# sensor_board_v0_91.net
KiCad netlist of a schematic drawn in EAGLE
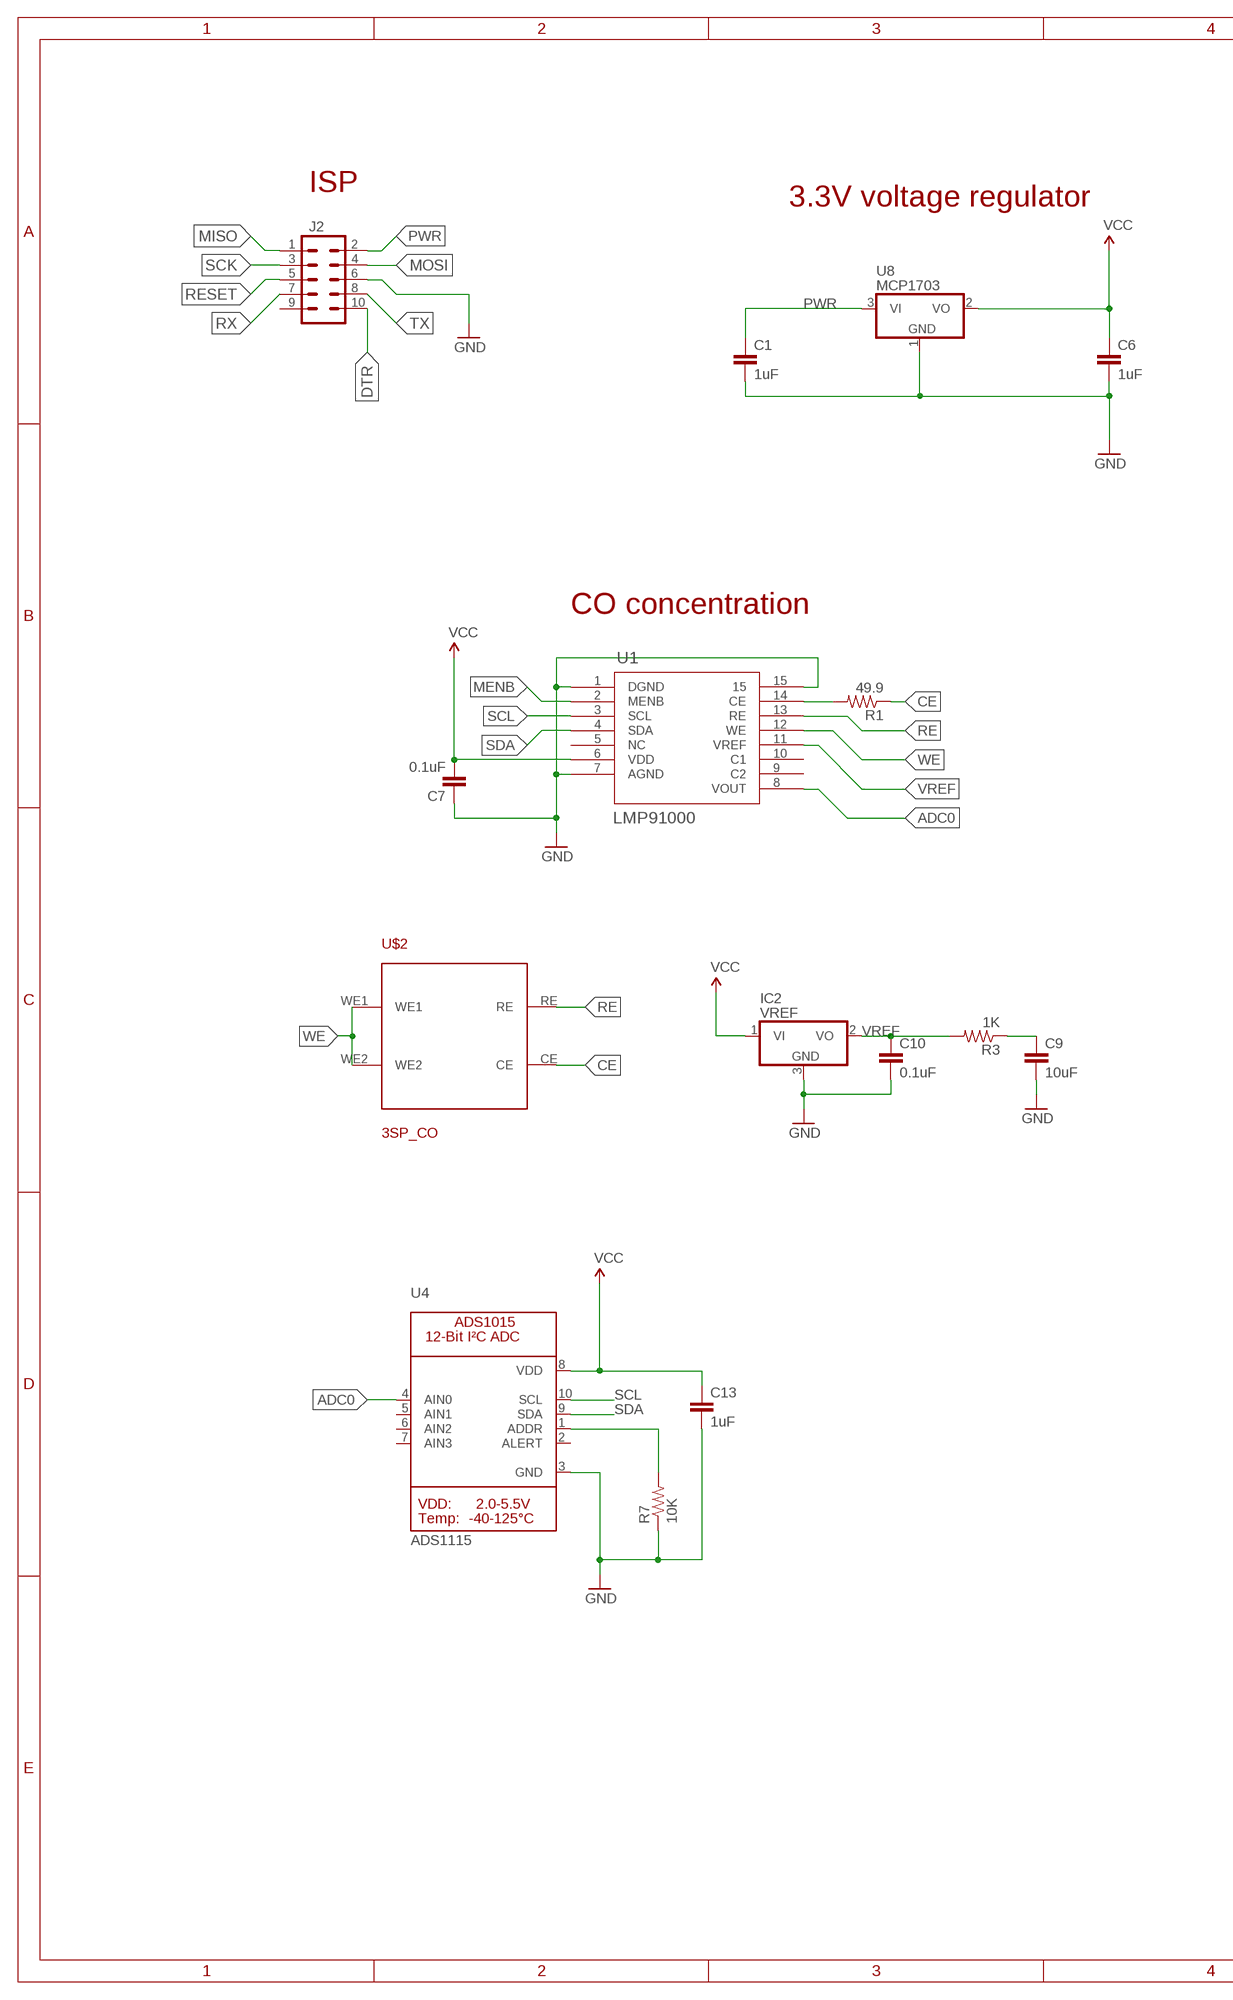
[diagram p0: schematic, sheet 1, part 1 of 2]
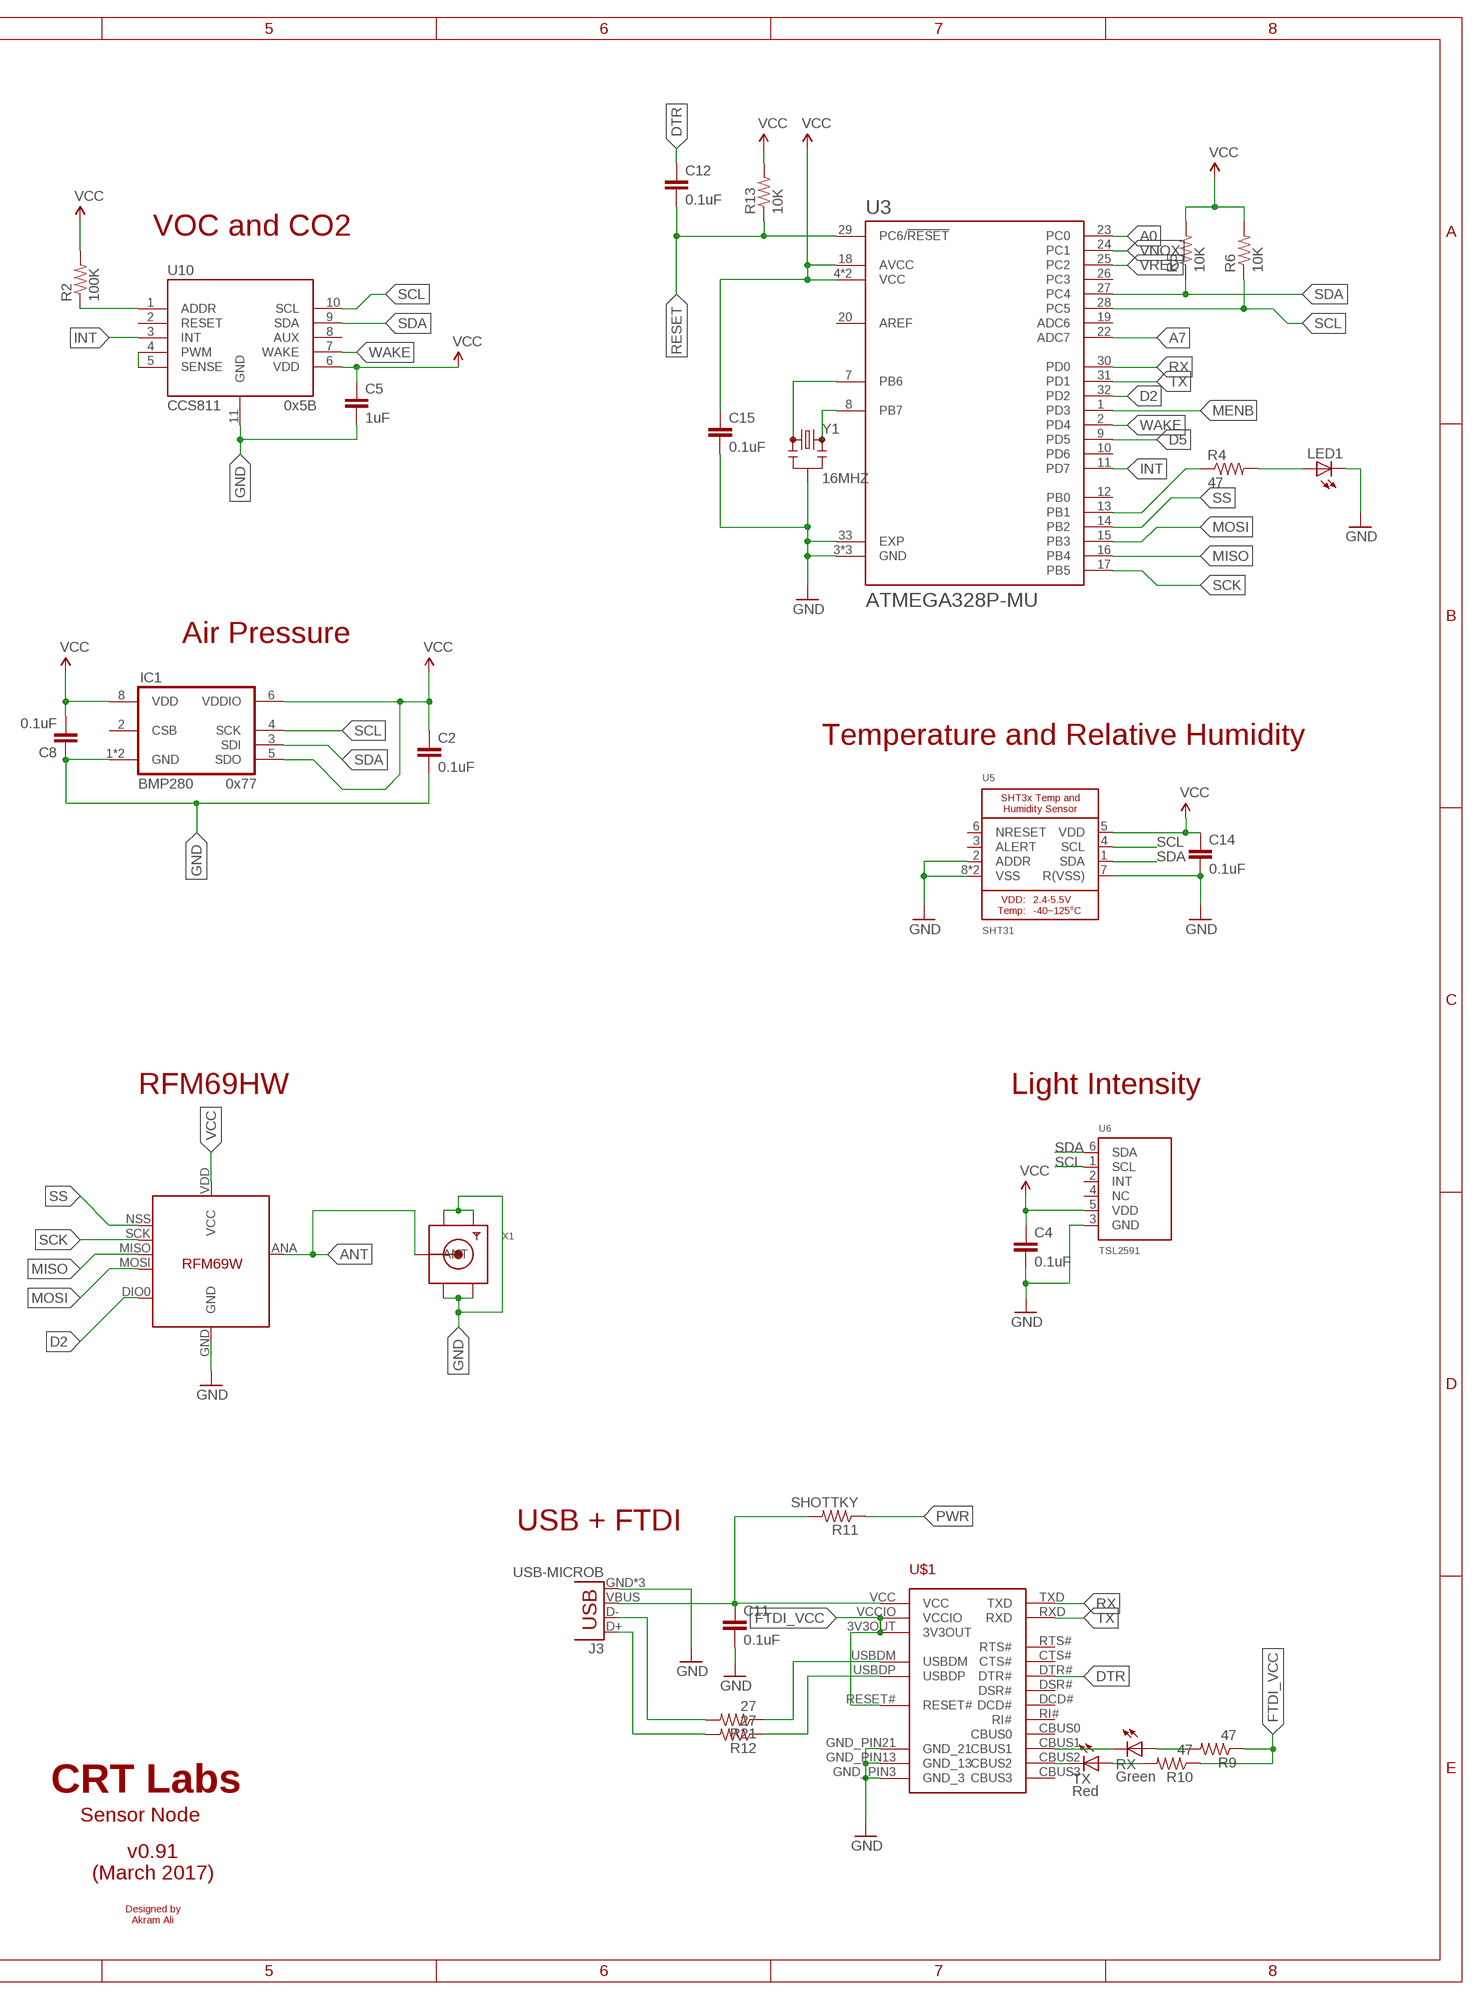
[diagram p1: schematic, sheet 1, part 2 of 2]

(export (version "E")
  (design (tool "Eeschema 10.0.6"))
  (components
    (comp (ref "C1")
      (value "1uF")
      (footprint "eagle-import:0805")
      (fields (field (name "MPN") "CC0805KKX7R7BB105"))
      (libsource (lib "eagle-import") (part "CAP0805"))
    )
    (comp (ref "C2")
      (value "0.1uF")
      (footprint "eagle-import:0805")
      (fields (field (name "MPN") "AC0805KRX7R9BB104"))
      (libsource (lib "eagle-import") (part "SparkFun-Passives_CAP0805"))
    )
    (comp (ref "C4")
      (value "0.1uF")
      (footprint "eagle-import:0805")
      (fields (field (name "MPN") "AC0805KRX7R9BB104"))
      (libsource (lib "eagle-import") (part "SparkFun-Passives_CAP0805"))
    )
    (comp (ref "C5")
      (value "1uF")
      (footprint "eagle-import:0805")
      (fields (field (name "MPN") "CC0805KKX7R7BB105"))
      (libsource (lib "eagle-import") (part "SparkFun-Passives_CAP0805"))
    )
    (comp (ref "C6")
      (value "1uF")
      (footprint "eagle-import:0805")
      (fields (field (name "MPN") "CC0805KKX7R7BB105"))
      (libsource (lib "eagle-import") (part "CAP0805"))
    )
    (comp (ref "C7")
      (value "0.1uF")
      (footprint "eagle-import:0805")
      (fields (field (name "MPN") "AC0805KRX7R9BB104"))
      (libsource (lib "eagle-import") (part "SparkFun-Passives_CAP0805"))
    )
    (comp (ref "C8")
      (value "0.1uF")
      (footprint "eagle-import:0805")
      (fields (field (name "MPN") "AC0805KRX7R9BB104"))
      (libsource (lib "eagle-import") (part "SparkFun-Passives_CAP0805"))
    )
    (comp (ref "C9")
      (value "10uF")
      (footprint "eagle-import:0805")
      (fields (field (name "MPN") "CC0805ZKY5V6BB106"))
      (libsource (lib "eagle-import") (part "SparkFun-Passives_CAP0805"))
    )
    (comp (ref "C10")
      (value "0.1uF")
      (footprint "eagle-import:0805")
      (fields (field (name "MPN") "AC0805KRX7R9BB104"))
      (libsource (lib "eagle-import") (part "SparkFun-Passives_CAP0805"))
    )
    (comp (ref "C11")
      (value "0.1uF")
      (footprint "eagle-import:0805")
      (fields (field (name "MPN") "AC0805KRX7R9BB104"))
      (libsource (lib "eagle-import") (part "CAP0805"))
    )
    (comp (ref "C12")
      (value "0.1uF")
      (footprint "eagle-import:0805")
      (fields (field (name "MPN") "AC0805KRX7R9BB104"))
      (libsource (lib "eagle-import") (part "SparkFun-Passives_CAP0805"))
    )
    (comp (ref "C13")
      (value "1uF")
      (footprint "eagle-import:0805")
      (fields (field (name "MPN") "CC0805KKX7R7BB105"))
      (libsource (lib "eagle-import") (part "SparkFun-Passives_CAP0805"))
    )
    (comp (ref "C14")
      (value "0.1uF")
      (footprint "eagle-import:0805")
      (fields (field (name "MPN") "AC0805KRX7R9BB104"))
      (libsource (lib "eagle-import") (part "SparkFun-Passives_CAP0805"))
    )
    (comp (ref "C15")
      (value "0.1uF")
      (footprint "eagle-import:0805")
      (fields (field (name "MPN") "AC0805KRX7R9BB104"))
      (libsource (lib "eagle-import") (part "SparkFun-Passives_CAP0805"))
    )
    (comp (ref "IC1")
      (value "BMP280")
      (footprint "eagle-import:BMP280")
      (libsource (lib "eagle-import") (part "BMP280"))
    )
    (comp (ref "IC2")
      (value "VREF")
      (footprint "eagle-import:SOT23")
      (fields (field (name "MPN") "ISL60002DIH320Z-TK"))
      (libsource (lib "eagle-import") (part "ISL60002DIH320ZCB"))
    )
    (comp (ref "J2")
      (value "M05X2PTH")
      (footprint "eagle-import:AVR_ICSP")
      (libsource (lib "eagle-import") (part "M05X2PTH"))
    )
    (comp (ref "J3")
      (value "USB-MICROB")
      (footprint "eagle-import:USB-MICROB")
      (fields (field (name "MPN") "CONN-09505"))
      (libsource (lib "eagle-import") (part "USB-MICROB"))
    )
    (comp (ref "LED1")
      (value "LEDCHIPLED_0805")
      (footprint "eagle-import:CHIPLED_0805")
      (fields (field (name "MPN") "150080BS75000"))
      (libsource (lib "eagle-import") (part "LEDCHIPLED_0805"))
    )
    (comp (ref "R1")
      (value "49.9")
      (footprint "eagle-import:0805")
      (fields (field (name "MPN") "RC0805FR-0749R9L"))
      (libsource (lib "eagle-import") (part "RESISTOR0805-RES"))
    )
    (comp (ref "R2")
      (value "100K")
      (footprint "eagle-import:0805")
      (fields (field (name "MPN") "311-100KCRCT-ND"))
      (libsource (lib "eagle-import") (part "RESISTOR0805-RES"))
    )
    (comp (ref "R3")
      (value "1K")
      (footprint "eagle-import:0805")
      (fields (field (name "MPN") "RC0805JR-071KL"))
      (libsource (lib "eagle-import") (part "RESISTOR0805-RES"))
    )
    (comp (ref "R4")
      (value "47")
      (footprint "eagle-import:0805")
      (fields (field (name "MPN") "RC0805JR-0747RL"))
      (libsource (lib "eagle-import") (part "SparkFun-Resistors_RESISTOR0805-RES"))
    )
    (comp (ref "R5")
      (value "10K")
      (footprint "eagle-import:0805")
      (fields (field (name "MPN") "RC0805JR-0710KL"))
      (libsource (lib "eagle-import") (part "SparkFun-Resistors_RESISTOR0805-RES"))
    )
    (comp (ref "R6")
      (value "10K")
      (footprint "eagle-import:0805")
      (fields (field (name "MPN") "RC0805JR-0710KL"))
      (libsource (lib "eagle-import") (part "SparkFun-Resistors_RESISTOR0805-RES"))
    )
    (comp (ref "R7")
      (value "10K")
      (footprint "eagle-import:0805")
      (fields (field (name "MPN") "RC0805JR-0710KL"))
      (libsource (lib "eagle-import") (part "SparkFun-Resistors_RESISTOR0805-RES"))
    )
    (comp (ref "R9")
      (value "47")
      (footprint "eagle-import:0805")
      (fields (field (name "MPN") "RC0805JR-0747RL"))
      (libsource (lib "eagle-import") (part "RESISTOR0805-RES"))
    )
    (comp (ref "R10")
      (value "47")
      (footprint "eagle-import:0805")
      (fields (field (name "MPN") "RC0805JR-0747RL"))
      (libsource (lib "eagle-import") (part "RESISTOR0805-RES"))
    )
    (comp (ref "R11")
      (value "SHOTTKY")
      (footprint "eagle-import:0805")
      (fields (field (name "MPN") "SD0805S020S0R5"))
      (libsource (lib "eagle-import") (part "RESISTOR0805-RES"))
    )
    (comp (ref "R12")
      (value "27")
      (footprint "eagle-import:0805")
      (fields (field (name "MPN") "RC0805FR-0727RL"))
      (libsource (lib "eagle-import") (part "RESISTOR0805-RES"))
    )
    (comp (ref "R13")
      (value "10K")
      (footprint "eagle-import:0805")
      (fields (field (name "MPN") "RC0805JR-0710KL"))
      (libsource (lib "eagle-import") (part "RESISTOR0805-RES"))
    )
    (comp (ref "R21")
      (value "27")
      (footprint "eagle-import:0805")
      (fields (field (name "MPN") "RC0805FR-0727RL"))
      (libsource (lib "eagle-import") (part "RESISTOR0805-RES"))
    )
    (comp (ref "RX")
      (value "Green")
      (footprint "eagle-import:CHIPLED_0805")
      (fields (field (name "MPN") "LG R971-KN-1"))
      (libsource (lib "eagle-import") (part "LEDCHIPLED_0805"))
    )
    (comp (ref "TX")
      (value "Red")
      (footprint "eagle-import:CHIPLED_0805")
      (fields (field (name "MPN") "LH R974-LP-1"))
      (libsource (lib "eagle-import") (part "LEDCHIPLED_0805"))
    )
    (comp (ref "U$1")
      (value "FT231XQ-R")
      (footprint "eagle-import:FTDI_FT231XQ-R_PACKAGE")
      (libsource (lib "eagle-import") (part "FT231XQ-R"))
    )
    (comp (ref "U$2")
      (value "3SP_CO")
      (footprint "eagle-import:3SP_CO_PIN_PACKAGE")
      (fields (field (name "MPN") "3SP CO"))
      (libsource (lib "eagle-import") (part "3SP_CO"))
    )
    (comp (ref "U1")
      (value "LMP91000")
      (footprint "eagle-import:SDA14B")
      (fields
        (field (name "MANUFACTURER") "Texas Instruments")
        (field (name "MANUFACTURER_PART_NUMBER") "lmp91000_nhl_14")
      )
      (libsource (lib "eagle-import") (part "LMP91000_NHL_14"))
    )
    (comp (ref "U3")
      (value "ATMEGA328P-MU")
      (footprint "eagle-import:QFN50P500X500X100-33N")
      (fields (field (name "MF") "Atmel"))
      (libsource (lib "eagle-import") (part "ATMEGA328P-MU"))
    )
    (comp (ref "U4")
      (value "ADS1115")
      (footprint "eagle-import:MSOP10")
      (libsource (lib "eagle-import") (part "ADC_ADS1015"))
    )
    (comp (ref "U5")
      (value "SHT31")
      (footprint "eagle-import:SHT3X")
      (libsource (lib "eagle-import") (part "SHT3X"))
    )
    (comp (ref "U6")
      (value "TSL2591")
      (footprint "eagle-import:DFN6_TAOS")
      (libsource (lib "eagle-import") (part "LIGHT_TSL2591"))
    )
    (comp (ref "U8")
      (value "MCP1703")
      (footprint "eagle-import:SOT23")
      (fields (field (name "MPN") "MCP1703T-2502E/CB"))
      (libsource (lib "eagle-import") (part "MCP1703CB"))
    )
    (comp (ref "U10")
      (value "CCS811")
      (footprint "eagle-import:LGA")
      (libsource (lib "eagle-import") (part "CCS811-I2C"))
    )
    (comp (ref "U11")
      (value "RFM69HW")
      (footprint "eagle-import:LOWPOWERLAB_RFM69W-MINPADS")
      (libsource (lib "eagle-import") (part "LOWPOWERLAB_RFM69"))
    )
    (comp (ref "X1")
      (value "SMACONNECTOR_EDGE")
      (footprint "eagle-import:SMA_EDGELAUNCH")
      (fields (field (name "MPN") "WRL-00593"))
      (libsource (lib "eagle-import") (part "SMACONNECTOR_EDGE"))
    )
    (comp (ref "Y1")
      (value "16MHZ")
      (footprint "eagle-import:RESONATOR-SMD")
      (fields (field (name "MPN") "CSTCE16M0V53-R0"))
      (libsource (lib "eagle-import") (part "RESONATOR16MHZ"))
    )
  )
  (nets
    (net (code "1") (name "A0") (class "Default")
      (node (ref "U3") (pin "23") (pinfunction "PC0_23") (pintype "bidirectional"))
    )
    (net (code "2") (name "A7") (class "Default")
      (node (ref "U3") (pin "22") (pinfunction "ADC7_22") (pintype "bidirectional"))
    )
    (net (code "3") (name "ADC0") (class "Default")
      (node (ref "U1") (pin "8") (pinfunction "VOUT_8") (pintype "output"))
      (node (ref "U4") (pin "4") (pinfunction "AIN0_4") (pintype "bidirectional"))
    )
    (net (code "4") (name "ANT") (class "Default")
      (node (ref "U11") (pin "ANA") (pinfunction "ANT_ANA") (pintype "passive"))
      (node (ref "X1") (pin "P") (pinfunction "ANT_P") (pintype "bidirectional"))
    )
    (net (code "5") (name "CE") (class "Default")
      (node (ref "R1") (pin "1") (pinfunction "1_1") (pintype "passive"))
      (node (ref "U$2") (pin "CE") (pinfunction "CE_CE") (pintype "bidirectional"))
    )
    (net (code "6") (name "D2") (class "Default")
      (node (ref "U11") (pin "DIO0") (pinfunction "DIO0_DIO0") (pintype "open_collector"))
      (node (ref "U3") (pin "32") (pinfunction "PD2_32") (pintype "bidirectional"))
    )
    (net (code "7") (name "D5") (class "Default")
      (node (ref "U3") (pin "9") (pinfunction "PD5_9") (pintype "bidirectional"))
    )
    (net (code "8") (name "DTR") (class "Default")
      (node (ref "C12") (pin "1") (pinfunction "1_1") (pintype "passive"))
      (node (ref "J2") (pin "10") (pinfunction "10_10") (pintype "passive"))
      (node (ref "U$1") (pin "DTR#") (pinfunction "DTR#_DTR#") (pintype "bidirectional"))
    )
    (net (code "9") (name "FTDI_VCC") (class "Default")
      (node (ref "R10") (pin "1") (pinfunction "1_1") (pintype "passive"))
      (node (ref "R9") (pin "1") (pinfunction "1_1") (pintype "passive"))
      (node (ref "U$1") (pin "3V3OUT") (pinfunction "3V3OUT_3V3OUT") (pintype "bidirectional"))
      (node (ref "U$1") (pin "RESET#") (pinfunction "RESET#_RESET#") (pintype "bidirectional"))
      (node (ref "U$1") (pin "VCCIO") (pinfunction "VCCIO_VCCIO") (pintype "bidirectional"))
    )
    (net (code "10") (name "GND") (class "Default")
      (node (ref "C1") (pin "2") (pinfunction "2_2") (pintype "passive"))
      (node (ref "C10") (pin "2") (pinfunction "2_2") (pintype "passive"))
      (node (ref "C11") (pin "2") (pinfunction "2_2") (pintype "passive"))
      (node (ref "C13") (pin "2") (pinfunction "2_2") (pintype "passive"))
      (node (ref "C14") (pin "2") (pinfunction "2_2") (pintype "passive"))
      (node (ref "C15") (pin "2") (pinfunction "2_2") (pintype "passive"))
      (node (ref "C2") (pin "2") (pinfunction "2_2") (pintype "passive"))
      (node (ref "C4") (pin "2") (pinfunction "2_2") (pintype "passive"))
      (node (ref "C5") (pin "2") (pinfunction "2_2") (pintype "passive"))
      (node (ref "C6") (pin "2") (pinfunction "2_2") (pintype "passive"))
      (node (ref "C7") (pin "1") (pinfunction "1_1") (pintype "passive"))
      (node (ref "C8") (pin "1") (pinfunction "1_1") (pintype "passive"))
      (node (ref "C9") (pin "2") (pinfunction "2_2") (pintype "passive"))
      (node (ref "IC1") (pin "1") (pinfunction "GND_1") (pintype "power_in"))
      (node (ref "IC1") (pin "7") (pinfunction "GND_7") (pintype "power_in"))
      (node (ref "IC2") (pin "3") (pinfunction "GND_3") (pintype "passive"))
      (node (ref "J2") (pin "6") (pinfunction "6_6") (pintype "passive"))
      (node (ref "J3") (pin "GND") (pinfunction "GND_GND") (pintype "bidirectional"))
      (node (ref "J3") (pin "MT1") (pinfunction "GND_MT1") (pintype "bidirectional"))
      (node (ref "J3") (pin "MT2") (pinfunction "GND_MT2") (pintype "bidirectional"))
      (node (ref "LED1") (pin "C") (pinfunction "C_C") (pintype "passive"))
      (node (ref "R7") (pin "1") (pinfunction "1_1") (pintype "passive"))
      (node (ref "U$1") (pin "GND_PIN13") (pinfunction "GND_13_GND_PIN13") (pintype "bidirectional"))
      (node (ref "U$1") (pin "GND_PIN21") (pinfunction "GND_21_GND_PIN21") (pintype "bidirectional"))
      (node (ref "U$1") (pin "GND_PIN3") (pinfunction "GND_3_GND_PIN3") (pintype "bidirectional"))
      (node (ref "U1") (pin "1") (pinfunction "DGND_1") (pintype "power_in"))
      (node (ref "U1") (pin "15") (pinfunction "15_15") (pintype "passive"))
      (node (ref "U1") (pin "7") (pinfunction "AGND_7") (pintype "power_in"))
      (node (ref "U10") (pin "11") (pinfunction "GND_11") (pintype "bidirectional"))
      (node (ref "U11") (pin "GND") (pinfunction "GND_GND") (pintype "power_in"))
      (node (ref "U3") (pin "21") (pinfunction "GND_21") (pintype "power_in"))
      (node (ref "U3") (pin "3") (pinfunction "GND_3") (pintype "power_in"))
      (node (ref "U3") (pin "33") (pinfunction "EXP_33") (pintype "power_in"))
      (node (ref "U3") (pin "5") (pinfunction "GND_5") (pintype "power_in"))
      (node (ref "U4") (pin "3") (pinfunction "GND_3") (pintype "bidirectional"))
      (node (ref "U5") (pin "2") (pinfunction "ADDR_2") (pintype "bidirectional"))
      (node (ref "U5") (pin "7") (pinfunction "R(VSS)_7") (pintype "bidirectional"))
      (node (ref "U5") (pin "8") (pinfunction "VSS_8") (pintype "power_in"))
      (node (ref "U5") (pin "THERMAL") (pinfunction "VSS_THERMAL") (pintype "power_in"))
      (node (ref "U6") (pin "3") (pinfunction "GND_3") (pintype "power_in"))
      (node (ref "U8") (pin "1") (pinfunction "GND_1") (pintype "passive"))
      (node (ref "X1") (pin "GND@1") (pinfunction "GND4_GND@1") (pintype "power_in"))
      (node (ref "X1") (pin "GND@2") (pinfunction "GND3_GND@2") (pintype "power_in"))
      (node (ref "X1") (pin "GND@3") (pinfunction "GND2_GND@3") (pintype "power_in"))
      (node (ref "X1") (pin "GND@4") (pinfunction "GND1_GND@4") (pintype "power_in"))
      (node (ref "Y1") (pin "2") (pinfunction "2_2") (pintype "passive"))
    )
    (net (code "11") (name "INT") (class "Default")
      (node (ref "U10") (pin "3") (pinfunction "INT_3") (pintype "bidirectional"))
      (node (ref "U3") (pin "11") (pinfunction "PD7_11") (pintype "bidirectional"))
    )
    (net (code "12") (name "MENB") (class "Default")
      (node (ref "U1") (pin "2") (pinfunction "MENB_2") (pintype "passive"))
      (node (ref "U3") (pin "1") (pinfunction "PD3_1") (pintype "bidirectional"))
    )
    (net (code "13") (name "MISO") (class "Default")
      (node (ref "J2") (pin "1") (pinfunction "1_1") (pintype "passive"))
      (node (ref "U11") (pin "MISO") (pinfunction "MISO_MISO") (pintype "input"))
      (node (ref "U3") (pin "16") (pinfunction "PB4_16") (pintype "bidirectional"))
    )
    (net (code "14") (name "MOSI") (class "Default")
      (node (ref "J2") (pin "4") (pinfunction "4_4") (pintype "passive"))
      (node (ref "U11") (pin "MOSI") (pinfunction "MOSI_MOSI") (pintype "output"))
      (node (ref "U3") (pin "15") (pinfunction "PB3_15") (pintype "bidirectional"))
    )
    (net (code "15") (name "Net-(C9-Pad1)") (class "Default")
      (node (ref "C9") (pin "1") (pinfunction "1_1") (pintype "passive"))
      (node (ref "R3") (pin "1") (pinfunction "1_1") (pintype "passive"))
    )
    (net (code "16") (name "Net-(C11-Pad1)") (class "Default")
      (node (ref "C11") (pin "1") (pinfunction "1_1") (pintype "passive"))
      (node (ref "J3") (pin "VBUS") (pinfunction "VBUS_VBUS") (pintype "bidirectional"))
      (node (ref "R11") (pin "2") (pinfunction "2_2") (pintype "passive"))
      (node (ref "U$1") (pin "VCC") (pinfunction "VCC_VCC") (pintype "bidirectional"))
    )
    (net (code "17") (name "Net-(J3-PadD+)") (class "Default")
      (node (ref "J3") (pin "D+") (pinfunction "D+_D+") (pintype "bidirectional"))
      (node (ref "R12") (pin "2") (pinfunction "2_2") (pintype "passive"))
    )
    (net (code "18") (name "Net-(J3-PadD-)") (class "Default")
      (node (ref "J3") (pin "D-") (pinfunction "D-_D-") (pintype "bidirectional"))
      (node (ref "R21") (pin "2") (pinfunction "2_2") (pintype "passive"))
    )
    (net (code "19") (name "Net-(LED1-PadA)") (class "Default")
      (node (ref "LED1") (pin "A") (pinfunction "A_A") (pintype "passive"))
      (node (ref "R4") (pin "2") (pinfunction "2_2") (pintype "passive"))
    )
    (net (code "20") (name "Net-(R9-Pad2)") (class "Default")
      (node (ref "R9") (pin "2") (pinfunction "2_2") (pintype "passive"))
      (node (ref "RX") (pin "A") (pinfunction "A_A") (pintype "passive"))
    )
    (net (code "21") (name "Net-(R10-Pad2)") (class "Default")
      (node (ref "R10") (pin "2") (pinfunction "2_2") (pintype "passive"))
      (node (ref "TX") (pin "A") (pinfunction "A_A") (pintype "passive"))
    )
    (net (code "22") (name "Net-(R12-Pad1)") (class "Default")
      (node (ref "R12") (pin "1") (pinfunction "1_1") (pintype "passive"))
      (node (ref "U$1") (pin "USBDP") (pinfunction "USBDP_USBDP") (pintype "bidirectional"))
    )
    (net (code "23") (name "Net-(R21-Pad1)") (class "Default")
      (node (ref "R21") (pin "1") (pinfunction "1_1") (pintype "passive"))
      (node (ref "U$1") (pin "USBDM") (pinfunction "USBDM_USBDM") (pintype "bidirectional"))
    )
    (net (code "24") (name "Net-(RX-PadC)") (class "Default")
      (node (ref "RX") (pin "C") (pinfunction "C_C") (pintype "passive"))
      (node (ref "U$1") (pin "CBUS1") (pinfunction "CBUS1_CBUS1") (pintype "bidirectional"))
    )
    (net (code "25") (name "Net-(TX-PadC)") (class "Default")
      (node (ref "TX") (pin "C") (pinfunction "C_C") (pintype "passive"))
      (node (ref "U$1") (pin "CBUS2") (pinfunction "CBUS2_CBUS2") (pintype "bidirectional"))
    )
    (net (code "26") (name "Net-(U1-CE)") (class "Default")
      (node (ref "R1") (pin "2") (pinfunction "2_2") (pintype "passive"))
      (node (ref "U1") (pin "14") (pinfunction "CE_14") (pintype "output"))
    )
    (net (code "27") (name "Net-(U3-PB1)") (class "Default")
      (node (ref "R4") (pin "1") (pinfunction "1_1") (pintype "passive"))
      (node (ref "U3") (pin "13") (pinfunction "PB1_13") (pintype "bidirectional"))
    )
    (net (code "28") (name "Net-(U3-PB6)") (class "Default")
      (node (ref "U3") (pin "7") (pinfunction "PB6_7") (pintype "bidirectional"))
      (node (ref "Y1") (pin "1") (pinfunction "1_1") (pintype "passive"))
    )
    (net (code "29") (name "Net-(U3-PB7)") (class "Default")
      (node (ref "U3") (pin "8") (pinfunction "PB7_8") (pintype "bidirectional"))
      (node (ref "Y1") (pin "3") (pinfunction "3_3") (pintype "passive"))
    )
    (net (code "30") (name "Net-(U4-ADDR)") (class "Default")
      (node (ref "R7") (pin "2") (pinfunction "2_2") (pintype "passive"))
      (node (ref "U4") (pin "1") (pinfunction "ADDR_1") (pintype "bidirectional"))
    )
    (net (code "31") (name "Net-(U10-ADDR)") (class "Default")
      (node (ref "R2") (pin "1") (pinfunction "1_1") (pintype "passive"))
      (node (ref "U10") (pin "1") (pinfunction "ADDR_1") (pintype "bidirectional"))
    )
    (net (code "32") (name "Net-(U10-PWM)") (class "Default")
      (node (ref "U10") (pin "4") (pinfunction "PWM_4") (pintype "bidirectional"))
      (node (ref "U10") (pin "5") (pinfunction "SENSE_5") (pintype "bidirectional"))
    )
    (net (code "33") (name "PWR") (class "Default")
      (node (ref "C1") (pin "1") (pinfunction "1_1") (pintype "passive"))
      (node (ref "J2") (pin "2") (pinfunction "2_2") (pintype "passive"))
      (node (ref "R11") (pin "1") (pinfunction "1_1") (pintype "passive"))
      (node (ref "U8") (pin "3") (pinfunction "VI_3") (pintype "input"))
    )
    (net (code "34") (name "RE") (class "Default")
      (node (ref "U$2") (pin "RE") (pinfunction "RE_RE") (pintype "bidirectional"))
      (node (ref "U1") (pin "13") (pinfunction "RE_13") (pintype "input"))
    )
    (net (code "35") (name "RESET") (class "Default")
      (node (ref "C12") (pin "2") (pinfunction "2_2") (pintype "passive"))
      (node (ref "J2") (pin "5") (pinfunction "5_5") (pintype "passive"))
      (node (ref "R13") (pin "1") (pinfunction "1_1") (pintype "passive"))
      (node (ref "U3") (pin "29") (pinfunction "PC6/~{RESET}_29") (pintype "bidirectional"))
    )
    (net (code "36") (name "RX") (class "Default")
      (node (ref "J2") (pin "7") (pinfunction "7_7") (pintype "passive"))
      (node (ref "U$1") (pin "TXD") (pinfunction "TXD_TXD") (pintype "bidirectional"))
      (node (ref "U3") (pin "30") (pinfunction "PD0_30") (pintype "bidirectional"))
    )
    (net (code "37") (name "SCK") (class "Default")
      (node (ref "J2") (pin "3") (pinfunction "3_3") (pintype "passive"))
      (node (ref "U11") (pin "SCK") (pinfunction "SCK_SCK") (pintype "input"))
      (node (ref "U3") (pin "17") (pinfunction "PB5_17") (pintype "bidirectional"))
    )
    (net (code "38") (name "SCL") (class "Default")
      (node (ref "IC1") (pin "4") (pinfunction "SCK_4") (pintype "bidirectional"))
      (node (ref "R6") (pin "1") (pinfunction "1_1") (pintype "passive"))
      (node (ref "U1") (pin "3") (pinfunction "SCL_3") (pintype "passive"))
      (node (ref "U10") (pin "10") (pinfunction "SCL_10") (pintype "bidirectional"))
      (node (ref "U3") (pin "28") (pinfunction "PC5_28") (pintype "bidirectional"))
      (node (ref "U4") (pin "10") (pinfunction "SCL_10") (pintype "bidirectional"))
      (node (ref "U5") (pin "4") (pinfunction "SCL_4") (pintype "bidirectional"))
      (node (ref "U6") (pin "1") (pinfunction "SCL_1") (pintype "bidirectional"))
    )
    (net (code "39") (name "SDA") (class "Default")
      (node (ref "IC1") (pin "3") (pinfunction "SDI_3") (pintype "bidirectional"))
      (node (ref "R5") (pin "1") (pinfunction "1_1") (pintype "passive"))
      (node (ref "U1") (pin "4") (pinfunction "SDA_4") (pintype "passive"))
      (node (ref "U10") (pin "9") (pinfunction "SDA_9") (pintype "bidirectional"))
      (node (ref "U3") (pin "27") (pinfunction "PC4_27") (pintype "bidirectional"))
      (node (ref "U4") (pin "9") (pinfunction "SDA_9") (pintype "bidirectional"))
      (node (ref "U5") (pin "1") (pinfunction "SDA_1") (pintype "bidirectional"))
      (node (ref "U6") (pin "6") (pinfunction "SDA_6") (pintype "bidirectional"))
    )
    (net (code "40") (name "SS") (class "Default")
      (node (ref "U11") (pin "NSS") (pinfunction "SEL_NSS") (pintype "input"))
      (node (ref "U3") (pin "14") (pinfunction "PB2_14") (pintype "bidirectional"))
    )
    (net (code "41") (name "TX") (class "Default")
      (node (ref "J2") (pin "8") (pinfunction "8_8") (pintype "passive"))
      (node (ref "U$1") (pin "RXD") (pinfunction "RXD_RXD") (pintype "bidirectional"))
      (node (ref "U3") (pin "31") (pinfunction "PD1_31") (pintype "bidirectional"))
    )
    (net (code "42") (name "VCC") (class "Default")
      (node (ref "C13") (pin "1") (pinfunction "1_1") (pintype "passive"))
      (node (ref "C14") (pin "1") (pinfunction "1_1") (pintype "passive"))
      (node (ref "C15") (pin "1") (pinfunction "1_1") (pintype "passive"))
      (node (ref "C2") (pin "1") (pinfunction "1_1") (pintype "passive"))
      (node (ref "C4") (pin "1") (pinfunction "1_1") (pintype "passive"))
      (node (ref "C5") (pin "1") (pinfunction "1_1") (pintype "passive"))
      (node (ref "C6") (pin "1") (pinfunction "1_1") (pintype "passive"))
      (node (ref "C7") (pin "2") (pinfunction "2_2") (pintype "passive"))
      (node (ref "C8") (pin "2") (pinfunction "2_2") (pintype "passive"))
      (node (ref "IC1") (pin "5") (pinfunction "SDO_5") (pintype "input"))
      (node (ref "IC1") (pin "6") (pinfunction "VDDIO_6") (pintype "power_in"))
      (node (ref "IC1") (pin "8") (pinfunction "VDD_8") (pintype "power_in"))
      (node (ref "IC2") (pin "1") (pinfunction "VI_1") (pintype "input"))
      (node (ref "R13") (pin "2") (pinfunction "2_2") (pintype "passive"))
      (node (ref "R2") (pin "2") (pinfunction "2_2") (pintype "passive"))
      (node (ref "R5") (pin "2") (pinfunction "2_2") (pintype "passive"))
      (node (ref "R6") (pin "2") (pinfunction "2_2") (pintype "passive"))
      (node (ref "U1") (pin "6") (pinfunction "VDD_6") (pintype "power_in"))
      (node (ref "U10") (pin "6") (pinfunction "VDD_6") (pintype "bidirectional"))
      (node (ref "U11") (pin "VDD") (pinfunction "VCC_VDD") (pintype "power_in"))
      (node (ref "U3") (pin "18") (pinfunction "AVCC_18") (pintype "power_in"))
      (node (ref "U3") (pin "4") (pinfunction "VCC_4") (pintype "power_in"))
      (node (ref "U3") (pin "6") (pinfunction "VCC_6") (pintype "power_in"))
      (node (ref "U4") (pin "8") (pinfunction "VDD_8") (pintype "bidirectional"))
      (node (ref "U5") (pin "5") (pinfunction "VDD_5") (pintype "power_in"))
      (node (ref "U6") (pin "5") (pinfunction "VDD_5") (pintype "power_in"))
      (node (ref "U8") (pin "2") (pinfunction "VO_2") (pintype "passive"))
    )
    (net (code "43") (name "VNOX") (class "Default")
      (node (ref "U3") (pin "24") (pinfunction "PC1_24") (pintype "bidirectional"))
    )
    (net (code "44") (name "VRED") (class "Default")
      (node (ref "U3") (pin "25") (pinfunction "PC2_25") (pintype "bidirectional"))
    )
    (net (code "45") (name "VREF") (class "Default")
      (node (ref "C10") (pin "1") (pinfunction "1_1") (pintype "passive"))
      (node (ref "IC2") (pin "2") (pinfunction "VO_2") (pintype "passive"))
      (node (ref "R3") (pin "2") (pinfunction "2_2") (pintype "passive"))
      (node (ref "U1") (pin "11") (pinfunction "VREF_11") (pintype "input"))
    )
    (net (code "46") (name "WAKE") (class "Default")
      (node (ref "U10") (pin "7") (pinfunction "WAKE_7") (pintype "bidirectional"))
      (node (ref "U3") (pin "2") (pinfunction "PD4_2") (pintype "bidirectional"))
    )
    (net (code "47") (name "WE") (class "Default")
      (node (ref "U$2") (pin "WE1") (pinfunction "WE1_WE1") (pintype "bidirectional"))
      (node (ref "U$2") (pin "WE2") (pinfunction "WE2_WE2") (pintype "bidirectional"))
      (node (ref "U1") (pin "12") (pinfunction "WE_12") (pintype "output"))
    )
    (net (code "48") (name "unconnected-(IC1-CSB-Pad2)") (class "Default")
      (node (ref "IC1") (pin "2") (pinfunction "CSB_2") (pintype "input"))
    )
    (net (code "49") (name "unconnected-(J2-Pad9)") (class "Default")
      (node (ref "J2") (pin "9") (pinfunction "9_9") (pintype "passive"))
    )
    (net (code "50") (name "unconnected-(U$1-PadCBUS0)") (class "Default")
      (node (ref "U$1") (pin "CBUS0") (pinfunction "CBUS0_CBUS0") (pintype "bidirectional"))
    )
    (net (code "51") (name "unconnected-(U$1-PadCBUS3)") (class "Default")
      (node (ref "U$1") (pin "CBUS3") (pinfunction "CBUS3_CBUS3") (pintype "bidirectional"))
    )
    (net (code "52") (name "unconnected-(U$1-PadCTS#)") (class "Default")
      (node (ref "U$1") (pin "CTS#") (pinfunction "CTS#_CTS#") (pintype "bidirectional"))
    )
    (net (code "53") (name "unconnected-(U$1-PadDCD#)") (class "Default")
      (node (ref "U$1") (pin "DCD#") (pinfunction "DCD#_DCD#") (pintype "bidirectional"))
    )
    (net (code "54") (name "unconnected-(U$1-PadDSR#)") (class "Default")
      (node (ref "U$1") (pin "DSR#") (pinfunction "DSR#_DSR#") (pintype "bidirectional"))
    )
    (net (code "55") (name "unconnected-(U$1-PadRI#)") (class "Default")
      (node (ref "U$1") (pin "RI#") (pinfunction "RI#_RI#") (pintype "bidirectional"))
    )
    (net (code "56") (name "unconnected-(U$1-PadRTS#)") (class "Default")
      (node (ref "U$1") (pin "RTS#") (pinfunction "RTS#_RTS#") (pintype "bidirectional"))
    )
    (net (code "57") (name "unconnected-(U1-C1-Pad10)") (class "Default")
      (node (ref "U1") (pin "10") (pinfunction "C1_10") (pintype "passive"))
    )
    (net (code "58") (name "unconnected-(U1-C2-Pad9)") (class "Default")
      (node (ref "U1") (pin "9") (pinfunction "C2_9") (pintype "passive"))
    )
    (net (code "59") (name "unconnected-(U1-NC-Pad5)") (class "Default")
      (node (ref "U1") (pin "5") (pinfunction "NC_5") (pintype "no_connect"))
    )
    (net (code "60") (name "unconnected-(U3-ADC6-Pad19)") (class "Default")
      (node (ref "U3") (pin "19") (pinfunction "ADC6_19") (pintype "bidirectional"))
    )
    (net (code "61") (name "unconnected-(U3-AREF-Pad20)") (class "Default")
      (node (ref "U3") (pin "20") (pinfunction "AREF_20") (pintype "input"))
    )
    (net (code "62") (name "unconnected-(U3-PB0-Pad12)") (class "Default")
      (node (ref "U3") (pin "12") (pinfunction "PB0_12") (pintype "bidirectional"))
    )
    (net (code "63") (name "unconnected-(U3-PC3-Pad26)") (class "Default")
      (node (ref "U3") (pin "26") (pinfunction "PC3_26") (pintype "bidirectional"))
    )
    (net (code "64") (name "unconnected-(U3-PD6-Pad10)") (class "Default")
      (node (ref "U3") (pin "10") (pinfunction "PD6_10") (pintype "bidirectional"))
    )
    (net (code "65") (name "unconnected-(U4-AIN1-Pad5)") (class "Default")
      (node (ref "U4") (pin "5") (pinfunction "AIN1_5") (pintype "bidirectional"))
    )
    (net (code "66") (name "unconnected-(U4-AIN2-Pad6)") (class "Default")
      (node (ref "U4") (pin "6") (pinfunction "AIN2_6") (pintype "bidirectional"))
    )
    (net (code "67") (name "unconnected-(U4-AIN3-Pad7)") (class "Default")
      (node (ref "U4") (pin "7") (pinfunction "AIN3_7") (pintype "bidirectional"))
    )
    (net (code "68") (name "unconnected-(U4-ALERT-Pad2)") (class "Default")
      (node (ref "U4") (pin "2") (pinfunction "ALERT_2") (pintype "bidirectional"))
    )
    (net (code "69") (name "unconnected-(U5-ALERT-Pad3)") (class "Default")
      (node (ref "U5") (pin "3") (pinfunction "ALERT_3") (pintype "bidirectional"))
    )
    (net (code "70") (name "unconnected-(U5-NRESET-Pad6)") (class "Default")
      (node (ref "U5") (pin "6") (pinfunction "NRESET_6") (pintype "bidirectional"))
    )
    (net (code "71") (name "unconnected-(U6-INT-Pad2)") (class "Default")
      (node (ref "U6") (pin "2") (pinfunction "INT_2") (pintype "output"))
    )
    (net (code "72") (name "unconnected-(U6-NC-Pad4)") (class "Default")
      (node (ref "U6") (pin "4") (pinfunction "NC_4") (pintype "no_connect"))
    )
    (net (code "73") (name "unconnected-(U10-AUX-Pad8)") (class "Default")
      (node (ref "U10") (pin "8") (pinfunction "AUX_8") (pintype "bidirectional"))
    )
    (net (code "74") (name "unconnected-(U10-RESET-Pad2)") (class "Default")
      (node (ref "U10") (pin "2") (pinfunction "RESET_2") (pintype "bidirectional"))
    )
  )
)
